# bbedison_base.net
KiCad netlist of a schematic drawn in EAGLE
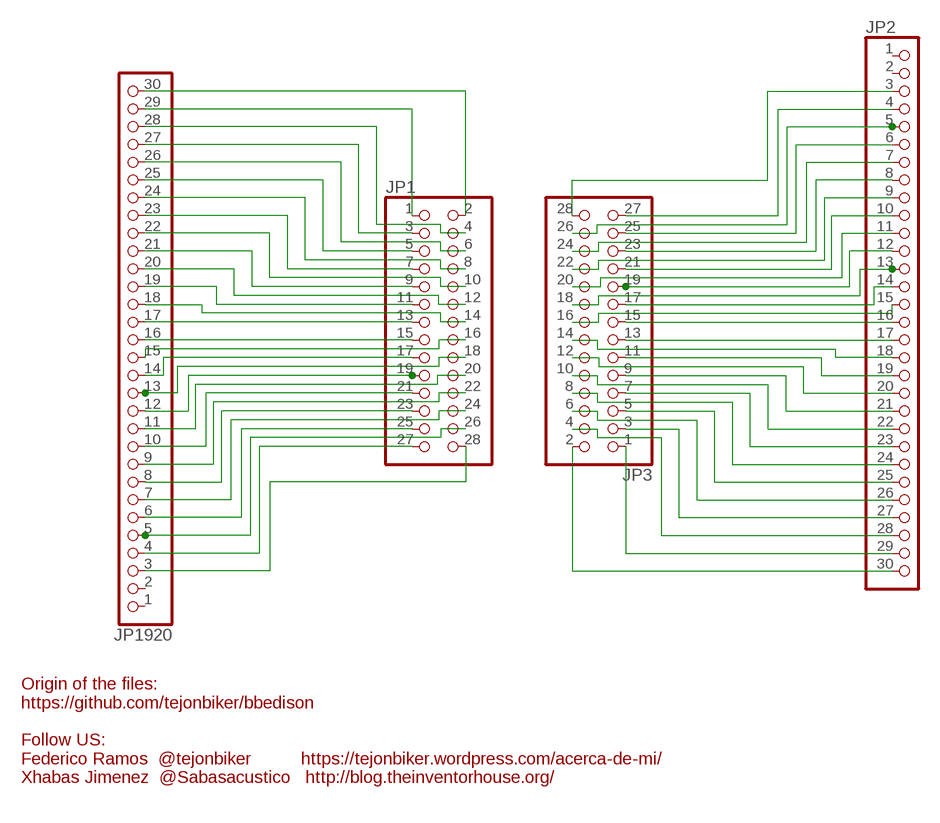
[diagram p0: schematic, sheet 1]

(export (version "E")
  (design (tool "Eeschema 10.0.6"))
  (components
    (comp (ref "JP1")
      (value "PINHD-2X14")
      (footprint "eagle-import:2X14")
      (libsource (lib "eagle-import") (part "PINHD-2X14"))
    )
    (comp (ref "JP2")
      (value "PINHD-1X30")
      (footprint "eagle-import:1X30")
      (libsource (lib "eagle-import") (part "PINHD-1X30"))
    )
    (comp (ref "JP3")
      (value "PINHD-2X14")
      (footprint "eagle-import:2X14")
      (libsource (lib "eagle-import") (part "PINHD-2X14"))
    )
    (comp (ref "JP1920")
      (value "PINHD-1X30")
      (footprint "eagle-import:1X30")
      (libsource (lib "eagle-import") (part "PINHD-1X30"))
    )
  )
  (nets
    (net (code "1") (name "Net-(JP1-Pad1)") (class "Default")
      (node (ref "JP1") (pin "1") (pinfunction "1_1") (pintype "passive"))
      (node (ref "JP1920") (pin "29") (pinfunction "29_29") (pintype "passive"))
    )
    (net (code "2") (name "Net-(JP1-Pad2)") (class "Default")
      (node (ref "JP1") (pin "2") (pinfunction "2_2") (pintype "passive"))
      (node (ref "JP1920") (pin "30") (pinfunction "30_30") (pintype "passive"))
    )
    (net (code "3") (name "Net-(JP1-Pad3)") (class "Default")
      (node (ref "JP1") (pin "3") (pinfunction "3_3") (pintype "passive"))
      (node (ref "JP1920") (pin "27") (pinfunction "27_27") (pintype "passive"))
    )
    (net (code "4") (name "Net-(JP1-Pad4)") (class "Default")
      (node (ref "JP1") (pin "4") (pinfunction "4_4") (pintype "passive"))
      (node (ref "JP1920") (pin "28") (pinfunction "28_28") (pintype "passive"))
    )
    (net (code "5") (name "Net-(JP1-Pad5)") (class "Default")
      (node (ref "JP1") (pin "5") (pinfunction "5_5") (pintype "passive"))
      (node (ref "JP1920") (pin "25") (pinfunction "25_25") (pintype "passive"))
    )
    (net (code "6") (name "Net-(JP1-Pad6)") (class "Default")
      (node (ref "JP1") (pin "6") (pinfunction "6_6") (pintype "passive"))
      (node (ref "JP1920") (pin "26") (pinfunction "26_26") (pintype "passive"))
    )
    (net (code "7") (name "Net-(JP1-Pad7)") (class "Default")
      (node (ref "JP1") (pin "7") (pinfunction "7_7") (pintype "passive"))
      (node (ref "JP1920") (pin "23") (pinfunction "23_23") (pintype "passive"))
    )
    (net (code "8") (name "Net-(JP1-Pad8)") (class "Default")
      (node (ref "JP1") (pin "8") (pinfunction "8_8") (pintype "passive"))
      (node (ref "JP1920") (pin "24") (pinfunction "24_24") (pintype "passive"))
    )
    (net (code "9") (name "Net-(JP1-Pad9)") (class "Default")
      (node (ref "JP1") (pin "9") (pinfunction "9_9") (pintype "passive"))
      (node (ref "JP1920") (pin "21") (pinfunction "21_21") (pintype "passive"))
    )
    (net (code "10") (name "Net-(JP1-Pad10)") (class "Default")
      (node (ref "JP1") (pin "10") (pinfunction "10_10") (pintype "passive"))
      (node (ref "JP1920") (pin "22") (pinfunction "22_22") (pintype "passive"))
    )
    (net (code "11") (name "Net-(JP1-Pad11)") (class "Default")
      (node (ref "JP1") (pin "11") (pinfunction "11_11") (pintype "passive"))
      (node (ref "JP1920") (pin "19") (pinfunction "19_19") (pintype "passive"))
    )
    (net (code "12") (name "Net-(JP1-Pad12)") (class "Default")
      (node (ref "JP1") (pin "12") (pinfunction "12_12") (pintype "passive"))
      (node (ref "JP1920") (pin "20") (pinfunction "20_20") (pintype "passive"))
    )
    (net (code "13") (name "Net-(JP1-Pad13)") (class "Default")
      (node (ref "JP1") (pin "13") (pinfunction "13_13") (pintype "passive"))
      (node (ref "JP1920") (pin "17") (pinfunction "17_17") (pintype "passive"))
    )
    (net (code "14") (name "Net-(JP1-Pad14)") (class "Default")
      (node (ref "JP1") (pin "14") (pinfunction "14_14") (pintype "passive"))
      (node (ref "JP1920") (pin "18") (pinfunction "18_18") (pintype "passive"))
    )
    (net (code "15") (name "Net-(JP1-Pad15)") (class "Default")
      (node (ref "JP1") (pin "15") (pinfunction "15_15") (pintype "passive"))
      (node (ref "JP1920") (pin "16") (pinfunction "16_16") (pintype "passive"))
    )
    (net (code "16") (name "Net-(JP1-Pad16)") (class "Default")
      (node (ref "JP1") (pin "16") (pinfunction "16_16") (pintype "passive"))
      (node (ref "JP1920") (pin "15") (pinfunction "15_15") (pintype "passive"))
    )
    (net (code "17") (name "Net-(JP1-Pad17)") (class "Default")
      (node (ref "JP1") (pin "17") (pinfunction "17_17") (pintype "passive"))
      (node (ref "JP1920") (pin "14") (pinfunction "14_14") (pintype "passive"))
    )
    (net (code "18") (name "Net-(JP1-Pad18)") (class "Default")
      (node (ref "JP1") (pin "18") (pinfunction "18_18") (pintype "passive"))
      (node (ref "JP1920") (pin "13") (pinfunction "13_13") (pintype "passive"))
    )
    (net (code "19") (name "Net-(JP1-Pad19)") (class "Default")
      (node (ref "JP1") (pin "19") (pinfunction "19_19") (pintype "passive"))
      (node (ref "JP1920") (pin "12") (pinfunction "12_12") (pintype "passive"))
    )
    (net (code "20") (name "Net-(JP1-Pad20)") (class "Default")
      (node (ref "JP1") (pin "20") (pinfunction "20_20") (pintype "passive"))
      (node (ref "JP1920") (pin "11") (pinfunction "11_11") (pintype "passive"))
    )
    (net (code "21") (name "Net-(JP1-Pad21)") (class "Default")
      (node (ref "JP1") (pin "21") (pinfunction "21_21") (pintype "passive"))
      (node (ref "JP1920") (pin "10") (pinfunction "10_10") (pintype "passive"))
    )
    (net (code "22") (name "Net-(JP1-Pad22)") (class "Default")
      (node (ref "JP1") (pin "22") (pinfunction "22_22") (pintype "passive"))
      (node (ref "JP1920") (pin "9") (pinfunction "9_9") (pintype "passive"))
    )
    (net (code "23") (name "Net-(JP1-Pad23)") (class "Default")
      (node (ref "JP1") (pin "23") (pinfunction "23_23") (pintype "passive"))
      (node (ref "JP1920") (pin "8") (pinfunction "8_8") (pintype "passive"))
    )
    (net (code "24") (name "Net-(JP1-Pad24)") (class "Default")
      (node (ref "JP1") (pin "24") (pinfunction "24_24") (pintype "passive"))
      (node (ref "JP1920") (pin "7") (pinfunction "7_7") (pintype "passive"))
    )
    (net (code "25") (name "Net-(JP1-Pad25)") (class "Default")
      (node (ref "JP1") (pin "25") (pinfunction "25_25") (pintype "passive"))
      (node (ref "JP1920") (pin "6") (pinfunction "6_6") (pintype "passive"))
    )
    (net (code "26") (name "Net-(JP1-Pad26)") (class "Default")
      (node (ref "JP1") (pin "26") (pinfunction "26_26") (pintype "passive"))
      (node (ref "JP1920") (pin "5") (pinfunction "5_5") (pintype "passive"))
    )
    (net (code "27") (name "Net-(JP1-Pad27)") (class "Default")
      (node (ref "JP1") (pin "27") (pinfunction "27_27") (pintype "passive"))
      (node (ref "JP1920") (pin "4") (pinfunction "4_4") (pintype "passive"))
    )
    (net (code "28") (name "Net-(JP1-Pad28)") (class "Default")
      (node (ref "JP1") (pin "28") (pinfunction "28_28") (pintype "passive"))
      (node (ref "JP1920") (pin "3") (pinfunction "3_3") (pintype "passive"))
    )
    (net (code "29") (name "Net-(JP2-Pad3)") (class "Default")
      (node (ref "JP2") (pin "3") (pinfunction "3_3") (pintype "passive"))
      (node (ref "JP3") (pin "28") (pinfunction "28_28") (pintype "passive"))
    )
    (net (code "30") (name "Net-(JP2-Pad4)") (class "Default")
      (node (ref "JP2") (pin "4") (pinfunction "4_4") (pintype "passive"))
      (node (ref "JP3") (pin "27") (pinfunction "27_27") (pintype "passive"))
    )
    (net (code "31") (name "Net-(JP2-Pad5)") (class "Default")
      (node (ref "JP2") (pin "5") (pinfunction "5_5") (pintype "passive"))
      (node (ref "JP3") (pin "26") (pinfunction "26_26") (pintype "passive"))
    )
    (net (code "32") (name "Net-(JP2-Pad6)") (class "Default")
      (node (ref "JP2") (pin "6") (pinfunction "6_6") (pintype "passive"))
      (node (ref "JP3") (pin "25") (pinfunction "25_25") (pintype "passive"))
    )
    (net (code "33") (name "Net-(JP2-Pad7)") (class "Default")
      (node (ref "JP2") (pin "7") (pinfunction "7_7") (pintype "passive"))
      (node (ref "JP3") (pin "24") (pinfunction "24_24") (pintype "passive"))
    )
    (net (code "34") (name "Net-(JP2-Pad8)") (class "Default")
      (node (ref "JP2") (pin "8") (pinfunction "8_8") (pintype "passive"))
      (node (ref "JP3") (pin "23") (pinfunction "23_23") (pintype "passive"))
    )
    (net (code "35") (name "Net-(JP2-Pad9)") (class "Default")
      (node (ref "JP2") (pin "9") (pinfunction "9_9") (pintype "passive"))
      (node (ref "JP3") (pin "22") (pinfunction "22_22") (pintype "passive"))
    )
    (net (code "36") (name "Net-(JP2-Pad10)") (class "Default")
      (node (ref "JP2") (pin "10") (pinfunction "10_10") (pintype "passive"))
      (node (ref "JP3") (pin "21") (pinfunction "21_21") (pintype "passive"))
    )
    (net (code "37") (name "Net-(JP2-Pad11)") (class "Default")
      (node (ref "JP2") (pin "11") (pinfunction "11_11") (pintype "passive"))
      (node (ref "JP3") (pin "20") (pinfunction "20_20") (pintype "passive"))
    )
    (net (code "38") (name "Net-(JP2-Pad12)") (class "Default")
      (node (ref "JP2") (pin "12") (pinfunction "12_12") (pintype "passive"))
      (node (ref "JP3") (pin "19") (pinfunction "19_19") (pintype "passive"))
    )
    (net (code "39") (name "Net-(JP2-Pad13)") (class "Default")
      (node (ref "JP2") (pin "13") (pinfunction "13_13") (pintype "passive"))
      (node (ref "JP3") (pin "18") (pinfunction "18_18") (pintype "passive"))
    )
    (net (code "40") (name "Net-(JP2-Pad14)") (class "Default")
      (node (ref "JP2") (pin "14") (pinfunction "14_14") (pintype "passive"))
      (node (ref "JP3") (pin "17") (pinfunction "17_17") (pintype "passive"))
    )
    (net (code "41") (name "Net-(JP2-Pad15)") (class "Default")
      (node (ref "JP2") (pin "15") (pinfunction "15_15") (pintype "passive"))
      (node (ref "JP3") (pin "16") (pinfunction "16_16") (pintype "passive"))
    )
    (net (code "42") (name "Net-(JP2-Pad16)") (class "Default")
      (node (ref "JP2") (pin "16") (pinfunction "16_16") (pintype "passive"))
      (node (ref "JP3") (pin "15") (pinfunction "15_15") (pintype "passive"))
    )
    (net (code "43") (name "Net-(JP2-Pad17)") (class "Default")
      (node (ref "JP2") (pin "17") (pinfunction "17_17") (pintype "passive"))
      (node (ref "JP3") (pin "13") (pinfunction "13_13") (pintype "passive"))
    )
    (net (code "44") (name "Net-(JP2-Pad18)") (class "Default")
      (node (ref "JP2") (pin "18") (pinfunction "18_18") (pintype "passive"))
      (node (ref "JP3") (pin "14") (pinfunction "14_14") (pintype "passive"))
    )
    (net (code "45") (name "Net-(JP2-Pad19)") (class "Default")
      (node (ref "JP2") (pin "19") (pinfunction "19_19") (pintype "passive"))
      (node (ref "JP3") (pin "11") (pinfunction "11_11") (pintype "passive"))
    )
    (net (code "46") (name "Net-(JP2-Pad20)") (class "Default")
      (node (ref "JP2") (pin "20") (pinfunction "20_20") (pintype "passive"))
      (node (ref "JP3") (pin "12") (pinfunction "12_12") (pintype "passive"))
    )
    (net (code "47") (name "Net-(JP2-Pad21)") (class "Default")
      (node (ref "JP2") (pin "21") (pinfunction "21_21") (pintype "passive"))
      (node (ref "JP3") (pin "9") (pinfunction "9_9") (pintype "passive"))
    )
    (net (code "48") (name "Net-(JP2-Pad22)") (class "Default")
      (node (ref "JP2") (pin "22") (pinfunction "22_22") (pintype "passive"))
      (node (ref "JP3") (pin "10") (pinfunction "10_10") (pintype "passive"))
    )
    (net (code "49") (name "Net-(JP2-Pad23)") (class "Default")
      (node (ref "JP2") (pin "23") (pinfunction "23_23") (pintype "passive"))
      (node (ref "JP3") (pin "7") (pinfunction "7_7") (pintype "passive"))
    )
    (net (code "50") (name "Net-(JP2-Pad24)") (class "Default")
      (node (ref "JP2") (pin "24") (pinfunction "24_24") (pintype "passive"))
      (node (ref "JP3") (pin "8") (pinfunction "8_8") (pintype "passive"))
    )
    (net (code "51") (name "Net-(JP2-Pad25)") (class "Default")
      (node (ref "JP2") (pin "25") (pinfunction "25_25") (pintype "passive"))
      (node (ref "JP3") (pin "5") (pinfunction "5_5") (pintype "passive"))
    )
    (net (code "52") (name "Net-(JP2-Pad26)") (class "Default")
      (node (ref "JP2") (pin "26") (pinfunction "26_26") (pintype "passive"))
      (node (ref "JP3") (pin "6") (pinfunction "6_6") (pintype "passive"))
    )
    (net (code "53") (name "Net-(JP2-Pad27)") (class "Default")
      (node (ref "JP2") (pin "27") (pinfunction "27_27") (pintype "passive"))
      (node (ref "JP3") (pin "3") (pinfunction "3_3") (pintype "passive"))
    )
    (net (code "54") (name "Net-(JP2-Pad28)") (class "Default")
      (node (ref "JP2") (pin "28") (pinfunction "28_28") (pintype "passive"))
      (node (ref "JP3") (pin "4") (pinfunction "4_4") (pintype "passive"))
    )
    (net (code "55") (name "Net-(JP2-Pad29)") (class "Default")
      (node (ref "JP2") (pin "29") (pinfunction "29_29") (pintype "passive"))
      (node (ref "JP3") (pin "1") (pinfunction "1_1") (pintype "passive"))
    )
    (net (code "56") (name "Net-(JP2-Pad30)") (class "Default")
      (node (ref "JP2") (pin "30") (pinfunction "30_30") (pintype "passive"))
      (node (ref "JP3") (pin "2") (pinfunction "2_2") (pintype "passive"))
    )
    (net (code "57") (name "unconnected-(JP2-Pad1)") (class "Default")
      (node (ref "JP2") (pin "1") (pinfunction "1_1") (pintype "passive"))
    )
    (net (code "58") (name "unconnected-(JP2-Pad2)") (class "Default")
      (node (ref "JP2") (pin "2") (pinfunction "2_2") (pintype "passive"))
    )
    (net (code "59") (name "unconnected-(JP1920-Pad1)") (class "Default")
      (node (ref "JP1920") (pin "1") (pinfunction "1_1") (pintype "passive"))
    )
    (net (code "60") (name "unconnected-(JP1920-Pad2)") (class "Default")
      (node (ref "JP1920") (pin "2") (pinfunction "2_2") (pintype "passive"))
    )
  )
)
